# ORD_BYPASS.net
KiCad netlist of a schematic drawn in Altium Designer
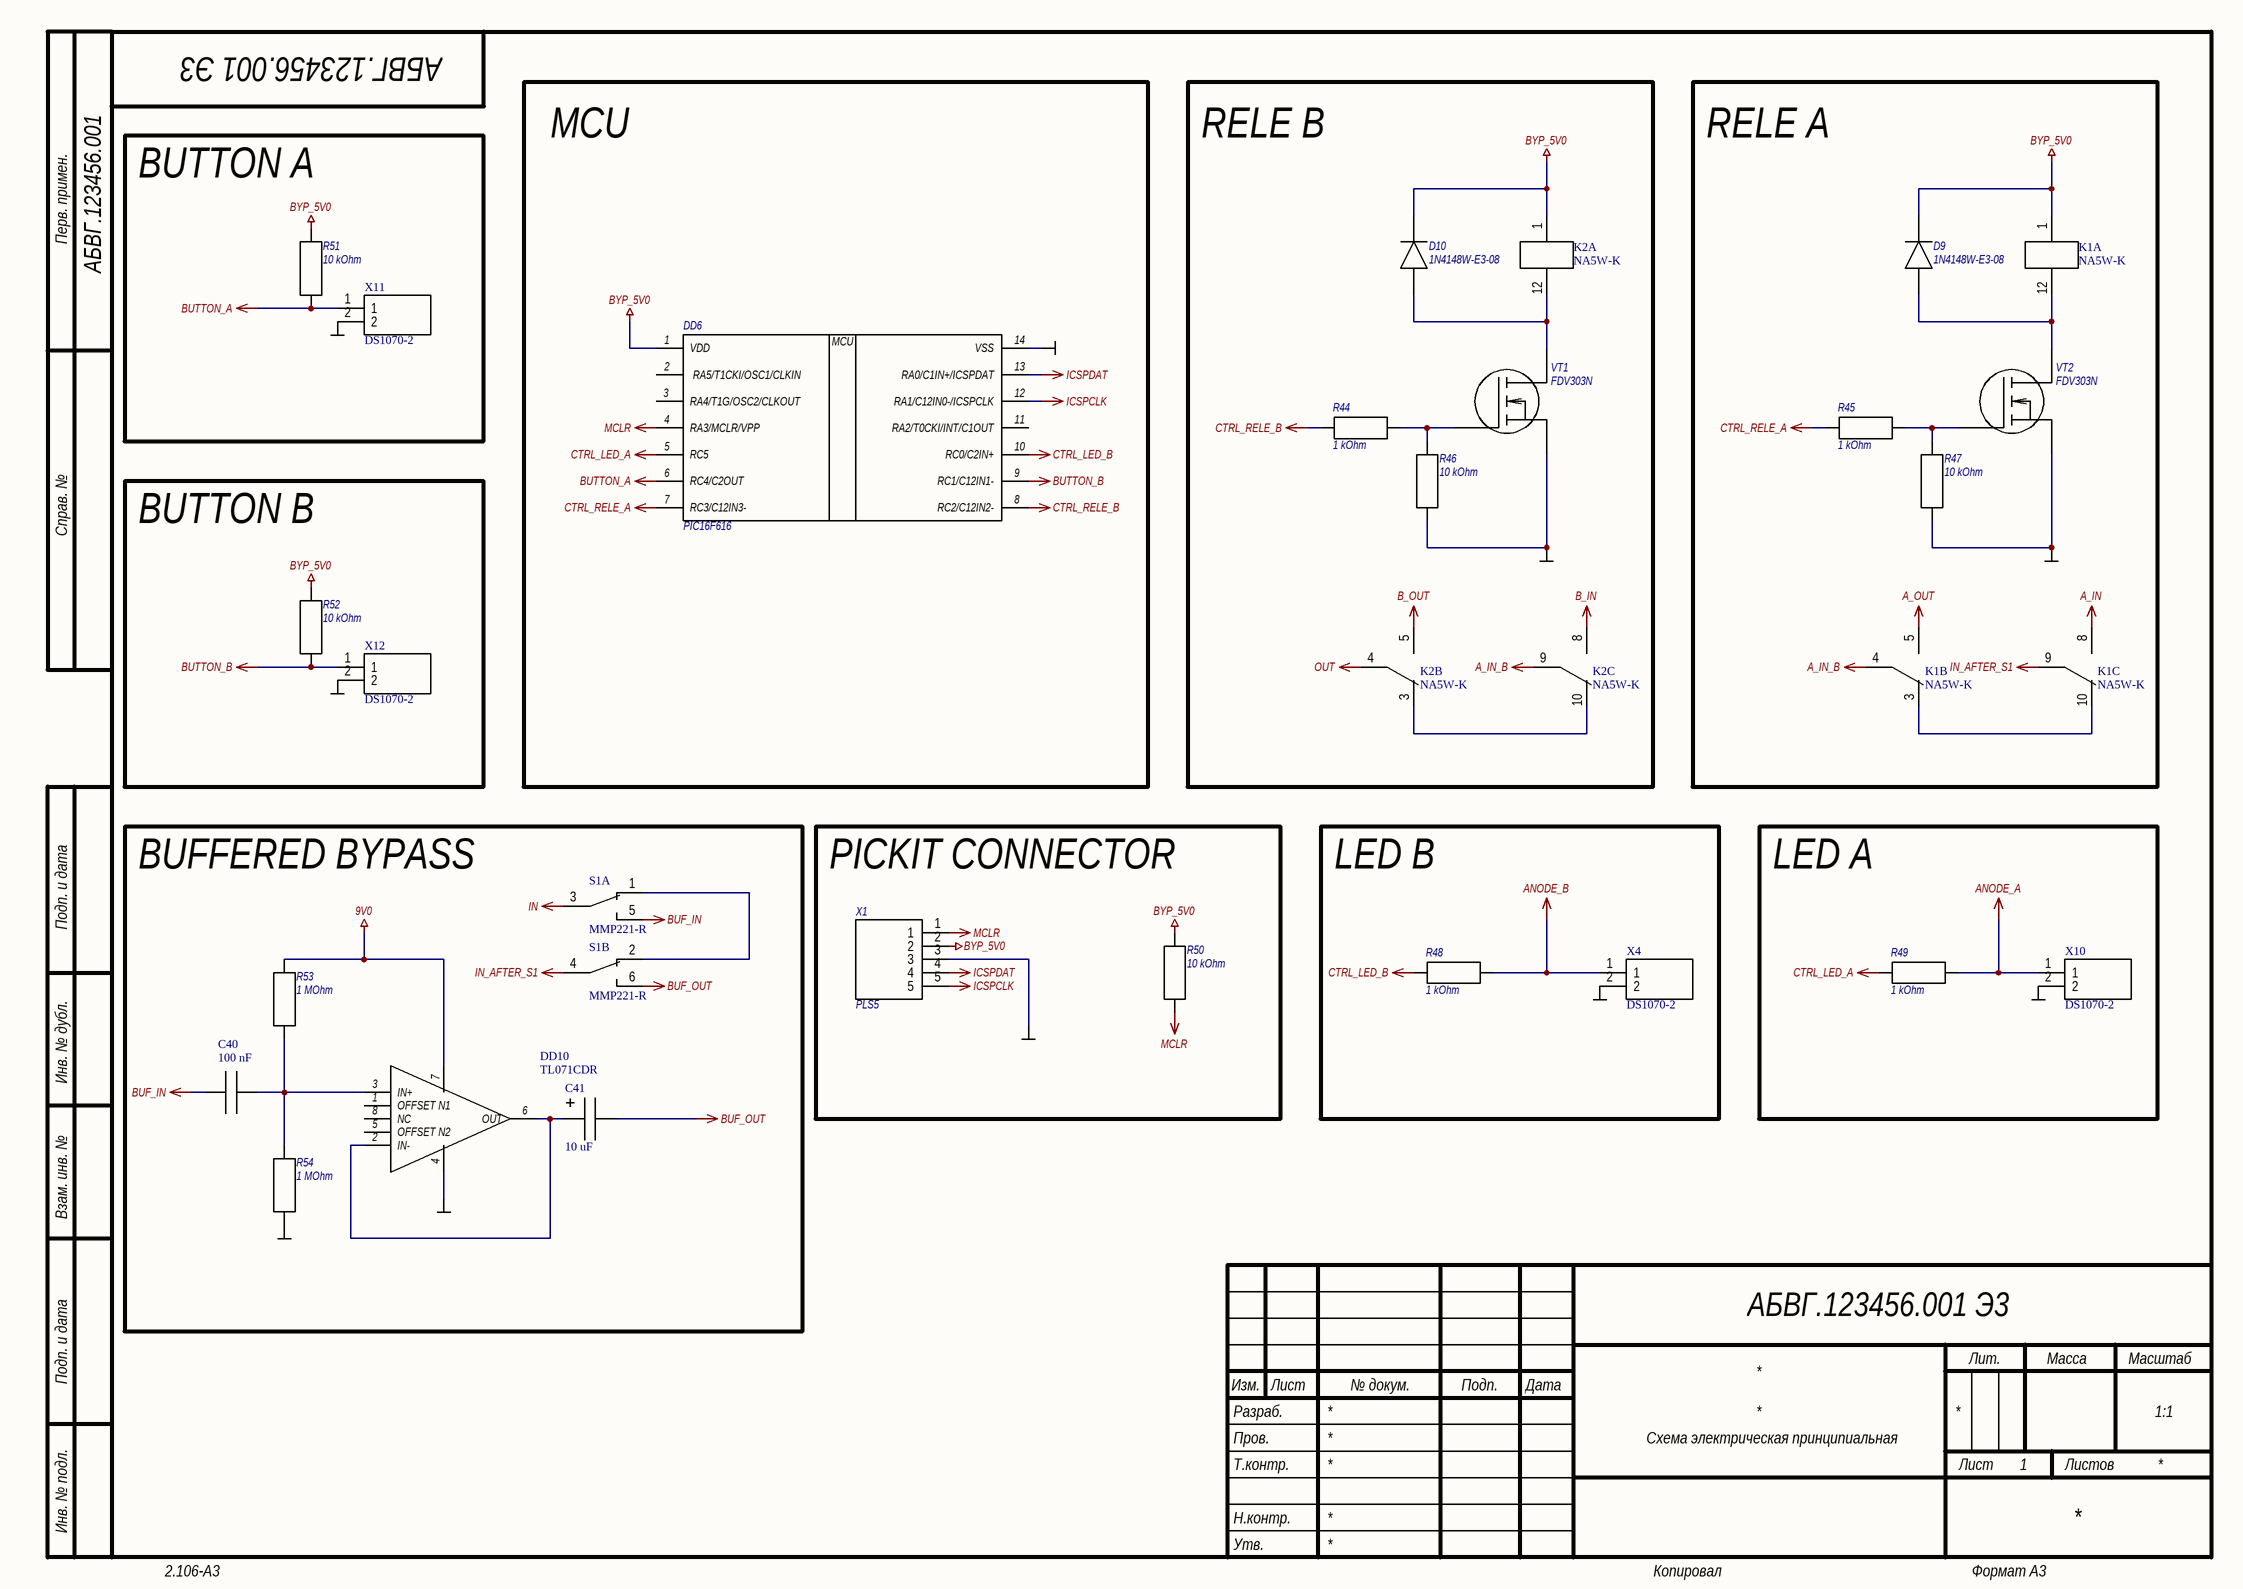
[diagram p0: ORD_BYPASS.SchDoc]

(export (version "E")
  (design (tool "Eeschema 10.0.6"))
  (components
    (comp (ref "C40")
      (value "100 nF")
      (footprint "C0805[2012]")
      (libsource (lib "Gost_passive_lib") (part "Capacitor"))
    )
    (comp (ref "C41")
      (value "10 uF")
      (footprint "C3216_CASE-A")
      (libsource (lib "Gost_passive_lib") (part "Capacitor_Pol"))
    )
    (comp (ref "D9")
      (value "1N4148W-E3-08")
      (footprint "SOD123")
      (description "Diode Switching 100V 0.15A SOD123 Vishay 1N4148W-E3-08 Switching Diode, 150mA 75V, 2-Pin SOD-123")
      (fields (field (name "RS PART NUMBER") "9189694"))
      (libsource (lib "Gost_passive_lib") (part "1N4148W-E3-08"))
    )
    (comp (ref "D10")
      (value "1N4148W-E3-08")
      (footprint "SOD123")
      (description "Diode Switching 100V 0.15A SOD123 Vishay 1N4148W-E3-08 Switching Diode, 150mA 75V, 2-Pin SOD-123")
      (fields (field (name "RS PART NUMBER") "9189694"))
      (libsource (lib "Gost_passive_lib") (part "1N4148W-E3-08"))
    )
    (comp (ref "DD6")
      (value "PIC16F616")
      (footprint "SO14")
      (description "Flash-Based 8-Bit\r\nCMOS Microcontroller")
      (fields
        (field (name "MANUFACTURER_PART_NUMBER") "LM386M-1/NOPB")
        (field (name "MOUSER PART NUMBER") "926-LM386M-1/NOPB")
      )
      (libsource (lib "Gost_active_libs") (part "PIC16F616"))
    )
    (comp (ref "DD10")
      (value "TL071CDR")
      (footprint "SO8")
      (description "TL071CDR, Operational Amplifier 4 MHz -18 to 18V, 8-Pin SO")
      (fields
        (field (name "MANUFACTURER_PART_NUMBER") "LM358DT")
        (field (name "MOUSER PART NUMBER") "511-LM358DT")
      )
      (libsource (lib "Gost_active_libs") (part "TL071CDR"))
    )
    (comp (ref "K1")
      (value "NA5W-K")
      (footprint "NA5W-K")
      (description "Low Signal Relays - PCB Mini Signal 5VDC")
      (fields
        (field (name "MANUFACTURER_PART_NUMBER") "NA-5W-K")
        (field (name "MOUSER PART NUMBER") "817-NA-5W-K")
      )
      (libsource (lib "Gost_passive_lib") (part "NA5W-K"))
    )
    (comp (ref "K2")
      (value "NA5W-K")
      (footprint "NA5W-K")
      (description "Low Signal Relays - PCB Mini Signal 5VDC")
      (fields
        (field (name "MANUFACTURER_PART_NUMBER") "NA-5W-K")
        (field (name "MOUSER PART NUMBER") "817-NA-5W-K")
      )
      (libsource (lib "Gost_passive_lib") (part "NA5W-K"))
    )
    (comp (ref "R44")
      (value "1 kOhm")
      (footprint "R0805[2012]")
      (libsource (lib "Gost_passive_lib") (part "Resistor"))
    )
    (comp (ref "R45")
      (value "1 kOhm")
      (footprint "R0805[2012]")
      (libsource (lib "Gost_passive_lib") (part "Resistor"))
    )
    (comp (ref "R46")
      (value "10 kOhm")
      (footprint "R0805[2012]")
      (libsource (lib "Gost_passive_lib") (part "Resistor"))
    )
    (comp (ref "R47")
      (value "10 kOhm")
      (footprint "R0805[2012]")
      (libsource (lib "Gost_passive_lib") (part "Resistor"))
    )
    (comp (ref "R48")
      (value "1 kOhm")
      (footprint "R0805[2012]")
      (libsource (lib "Gost_passive_lib") (part "Resistor"))
    )
    (comp (ref "R49")
      (value "1 kOhm")
      (footprint "R0805[2012]")
      (libsource (lib "Gost_passive_lib") (part "Resistor"))
    )
    (comp (ref "R50")
      (value "10 kOhm")
      (footprint "R0805[2012]")
      (libsource (lib "Gost_passive_lib") (part "Resistor"))
    )
    (comp (ref "R51")
      (value "10 kOhm")
      (footprint "R0805[2012]")
      (libsource (lib "Gost_passive_lib") (part "Resistor"))
    )
    (comp (ref "R52")
      (value "10 kOhm")
      (footprint "R0805[2012]")
      (libsource (lib "Gost_passive_lib") (part "Resistor"))
    )
    (comp (ref "R53")
      (value "1 MOhm")
      (footprint "R0805[2012]")
      (libsource (lib "Gost_passive_lib") (part "Resistor"))
    )
    (comp (ref "R54")
      (value "1 MOhm")
      (footprint "R0805[2012]")
      (libsource (lib "Gost_passive_lib") (part "Resistor"))
    )
    (comp (ref "S1")
      (value "MMP221-R")
      (footprint "MMP221R")
      (description "PCB Slide Switch DPDT On-On 200 mA @ 12 V dc Slide")
      (fields (field (name "RS PART NUMBER") "7023564P"))
      (libsource (lib "Gost_connectors_lib") (part "MMP221-R"))
    )
    (comp (ref "VT1")
      (value "FDV303N")
      (footprint "SOT-23")
      (description "N - channel power mosfet")
      (libsource (lib "Gost_passive_lib") (part "FDV303N"))
    )
    (comp (ref "VT2")
      (value "FDV303N")
      (footprint "SOT-23")
      (description "N - channel power mosfet")
      (libsource (lib "Gost_passive_lib") (part "FDV303N"))
    )
    (comp (ref "X1")
      (value "PLS5")
      (footprint "PLS-5 (UP)")
      (description "2.54 mm")
      (libsource (lib "Gost_connectors_lib") (part "PLS5"))
    )
    (comp (ref "X4")
      (value "DS1070-2")
      (footprint "DS1070-2")
      (description "2.54 mm, male")
      (libsource (lib "Gost_connectors_lib") (part "DS1070-2"))
    )
    (comp (ref "X10")
      (value "DS1070-2")
      (footprint "DS1070-2")
      (description "2.54 mm, male")
      (libsource (lib "Gost_connectors_lib") (part "DS1070-2"))
    )
    (comp (ref "X11")
      (value "DS1070-2")
      (footprint "DS1070-2")
      (description "2.54 mm, male")
      (libsource (lib "Gost_connectors_lib") (part "DS1070-2"))
    )
    (comp (ref "X12")
      (value "DS1070-2")
      (footprint "DS1070-2")
      (description "2.54 mm, male")
      (libsource (lib "Gost_connectors_lib") (part "DS1070-2"))
    )
  )
  (nets
    (net (code "1") (name "9V0") (class "Default")
      (node (ref "DD10") (pin "7") (pinfunction "VCC+_7") (pintype "passive"))
      (node (ref "R53") (pin "2") (pinfunction "2_2") (pintype "passive"))
    )
    (net (code "2") (name "ANODE_A") (class "Default")
      (node (ref "R49") (pin "2") (pinfunction "2_2") (pintype "passive"))
      (node (ref "X10") (pin "1") (pinfunction "1_1") (pintype "power_in"))
    )
    (net (code "3") (name "ANODE_B") (class "Default")
      (node (ref "R48") (pin "2") (pinfunction "2_2") (pintype "passive"))
      (node (ref "X4") (pin "1") (pinfunction "1_1") (pintype "power_in"))
    )
    (net (code "4") (name "A_IN") (class "Default")
      (node (ref "K1") (pin "8") (pinfunction "NO_2_8") (pintype "passive"))
    )
    (net (code "5") (name "A_IN_B") (class "Default")
      (node (ref "K1") (pin "4") (pinfunction "COM_1_4") (pintype "passive"))
      (node (ref "K2") (pin "9") (pinfunction "COM_2_9") (pintype "passive"))
    )
    (net (code "6") (name "A_OUT") (class "Default")
      (node (ref "K1") (pin "5") (pinfunction "NO_1_5") (pintype "passive"))
    )
    (net (code "7") (name "BUF_IN") (class "Default")
      (node (ref "C40") (pin "1") (pinfunction "1_1") (pintype "passive"))
      (node (ref "S1") (pin "5") (pinfunction "NO_1_5") (pintype "passive"))
    )
    (net (code "8") (name "BUF_OUT") (class "Default")
      (node (ref "C41") (pin "2") (pinfunction "2_2") (pintype "passive"))
      (node (ref "S1") (pin "6") (pinfunction "NO_2_6") (pintype "passive"))
    )
    (net (code "9") (name "BUTTON_A") (class "Default")
      (node (ref "DD6") (pin "6") (pinfunction "RC4/C2OUT_6") (pintype "passive"))
      (node (ref "R51") (pin "1") (pinfunction "1_1") (pintype "passive"))
      (node (ref "X11") (pin "1") (pinfunction "1_1") (pintype "power_in"))
    )
    (net (code "10") (name "BUTTON_B") (class "Default")
      (node (ref "DD6") (pin "9") (pinfunction "RC1/C12IN1-_9") (pintype "passive"))
      (node (ref "R52") (pin "1") (pinfunction "1_1") (pintype "passive"))
      (node (ref "X12") (pin "1") (pinfunction "1_1") (pintype "power_in"))
    )
    (net (code "11") (name "BYP_5V0") (class "Default")
      (node (ref "D10") (pin "1") (pinfunction "K_1") (pintype "passive"))
      (node (ref "D9") (pin "1") (pinfunction "K_1") (pintype "passive"))
      (node (ref "DD6") (pin "1") (pinfunction "VDD_1") (pintype "passive"))
      (node (ref "K1") (pin "1") (pinfunction "+(-)_1") (pintype "passive"))
      (node (ref "K2") (pin "1") (pinfunction "+(-)_1") (pintype "passive"))
      (node (ref "R50") (pin "2") (pinfunction "2_2") (pintype "passive"))
      (node (ref "R51") (pin "2") (pinfunction "2_2") (pintype "passive"))
      (node (ref "R52") (pin "2") (pinfunction "2_2") (pintype "passive"))
      (node (ref "X1") (pin "2") (pinfunction "2_2") (pintype "power_in"))
    )
    (net (code "12") (name "B_IN") (class "Default")
      (node (ref "K2") (pin "8") (pinfunction "NO_2_8") (pintype "passive"))
    )
    (net (code "13") (name "B_OUT") (class "Default")
      (node (ref "K2") (pin "5") (pinfunction "NO_1_5") (pintype "passive"))
    )
    (net (code "14") (name "CTRL_LED_A") (class "Default")
      (node (ref "DD6") (pin "5") (pinfunction "RC5_5") (pintype "passive"))
      (node (ref "R49") (pin "1") (pinfunction "1_1") (pintype "passive"))
    )
    (net (code "15") (name "CTRL_LED_B") (class "Default")
      (node (ref "DD6") (pin "10") (pinfunction "RC0/C2IN+_10") (pintype "passive"))
      (node (ref "R48") (pin "1") (pinfunction "1_1") (pintype "passive"))
    )
    (net (code "16") (name "CTRL_RELE_A") (class "Default")
      (node (ref "DD6") (pin "7") (pinfunction "RC3/C12IN3-_7") (pintype "passive"))
      (node (ref "R45") (pin "1") (pinfunction "1_1") (pintype "passive"))
    )
    (net (code "17") (name "CTRL_RELE_B") (class "Default")
      (node (ref "DD6") (pin "8") (pinfunction "RC2/C12IN2-_8") (pintype "passive"))
      (node (ref "R44") (pin "1") (pinfunction "1_1") (pintype "passive"))
    )
    (net (code "18") (name "GND") (class "Default")
      (node (ref "DD10") (pin "4") (pinfunction "VCC-_4") (pintype "passive"))
      (node (ref "DD6") (pin "14") (pinfunction "VSS_14") (pintype "passive"))
      (node (ref "R46") (pin "1") (pinfunction "1_1") (pintype "passive"))
      (node (ref "R47") (pin "1") (pinfunction "1_1") (pintype "passive"))
      (node (ref "R54") (pin "1") (pinfunction "1_1") (pintype "passive"))
      (node (ref "VT1") (pin "2") (pinfunction "S_2") (pintype "passive"))
      (node (ref "VT2") (pin "2") (pinfunction "S_2") (pintype "passive"))
      (node (ref "X1") (pin "3") (pinfunction "3_3") (pintype "power_in"))
      (node (ref "X10") (pin "2") (pinfunction "2_2") (pintype "power_in"))
      (node (ref "X11") (pin "2") (pinfunction "2_2") (pintype "power_in"))
      (node (ref "X12") (pin "2") (pinfunction "2_2") (pintype "power_in"))
      (node (ref "X4") (pin "2") (pinfunction "2_2") (pintype "power_in"))
    )
    (net (code "19") (name "ICSPCLK") (class "Default")
      (node (ref "DD6") (pin "12") (pinfunction "RA1/C12IN0-/ICSPCLK_12") (pintype "passive"))
      (node (ref "X1") (pin "5") (pinfunction "5_5") (pintype "power_in"))
    )
    (net (code "20") (name "ICSPDAT") (class "Default")
      (node (ref "DD6") (pin "13") (pinfunction "RA0/C1IN+/ICSPDAT_13") (pintype "passive"))
      (node (ref "X1") (pin "4") (pinfunction "4_4") (pintype "power_in"))
    )
    (net (code "21") (name "IN") (class "Default")
      (node (ref "S1") (pin "3") (pinfunction "C_1_3") (pintype "passive"))
    )
    (net (code "22") (name "IN_AFTER_S1") (class "Default")
      (node (ref "K1") (pin "9") (pinfunction "COM_2_9") (pintype "passive"))
      (node (ref "S1") (pin "4") (pinfunction "C_2_4") (pintype "passive"))
    )
    (net (code "23") (name "MCLR") (class "Default")
      (node (ref "DD6") (pin "4") (pinfunction "RA3/MCLR/VPP_4") (pintype "passive"))
      (node (ref "R50") (pin "1") (pinfunction "1_1") (pintype "passive"))
      (node (ref "X1") (pin "1") (pinfunction "1_1") (pintype "power_in"))
    )
    (net (code "24") (name "Net-(D9-A)") (class "Default")
      (node (ref "D9") (pin "2") (pinfunction "A_2") (pintype "passive"))
      (node (ref "K1") (pin "12") (pinfunction "-(+)_12") (pintype "passive"))
      (node (ref "VT2") (pin "3") (pinfunction "D_3") (pintype "passive"))
    )
    (net (code "25") (name "Net-(D10-A)") (class "Default")
      (node (ref "D10") (pin "2") (pinfunction "A_2") (pintype "passive"))
      (node (ref "K2") (pin "12") (pinfunction "-(+)_12") (pintype "passive"))
      (node (ref "VT1") (pin "3") (pinfunction "D_3") (pintype "passive"))
    )
    (net (code "26") (name "Net-(DD10-IN+)") (class "Default")
      (node (ref "C40") (pin "2") (pinfunction "2_2") (pintype "passive"))
      (node (ref "DD10") (pin "3") (pinfunction "IN+_3") (pintype "passive"))
      (node (ref "R53") (pin "1") (pinfunction "1_1") (pintype "passive"))
      (node (ref "R54") (pin "2") (pinfunction "2_2") (pintype "passive"))
    )
    (net (code "27") (name "Net-(DD10-IN-)") (class "Default")
      (node (ref "C41") (pin "1") (pinfunction "1_1") (pintype "passive"))
      (node (ref "DD10") (pin "2") (pinfunction "IN-_2") (pintype "passive"))
      (node (ref "DD10") (pin "6") (pinfunction "OUT_6") (pintype "passive"))
    )
    (net (code "28") (name "Net-(K1B-NC_1)") (class "Default")
      (node (ref "K1") (pin "10") (pinfunction "NC_2_10") (pintype "passive"))
      (node (ref "K1") (pin "3") (pinfunction "NC_1_3") (pintype "passive"))
    )
    (net (code "29") (name "Net-(K2B-NC_1)") (class "Default")
      (node (ref "K2") (pin "10") (pinfunction "NC_2_10") (pintype "passive"))
      (node (ref "K2") (pin "3") (pinfunction "NC_1_3") (pintype "passive"))
    )
    (net (code "30") (name "Net-(S1A-NC_1)") (class "Default")
      (node (ref "S1") (pin "1") (pinfunction "NC_1_1") (pintype "passive"))
      (node (ref "S1") (pin "2") (pinfunction "NC_2_2") (pintype "passive"))
    )
    (net (code "31") (name "Net-(VT1-G)") (class "Default")
      (node (ref "R44") (pin "2") (pinfunction "2_2") (pintype "passive"))
      (node (ref "R46") (pin "2") (pinfunction "2_2") (pintype "passive"))
      (node (ref "VT1") (pin "1") (pinfunction "G_1") (pintype "passive"))
    )
    (net (code "32") (name "Net-(VT2-G)") (class "Default")
      (node (ref "R45") (pin "2") (pinfunction "2_2") (pintype "passive"))
      (node (ref "R47") (pin "2") (pinfunction "2_2") (pintype "passive"))
      (node (ref "VT2") (pin "1") (pinfunction "G_1") (pintype "passive"))
    )
    (net (code "33") (name "OUT") (class "Default")
      (node (ref "K2") (pin "4") (pinfunction "COM_1_4") (pintype "passive"))
    )
    (net (code "34") (name "unconnected-(DD6-RA2{slash}T0CKI{slash}INT{slash}C1OUT-Pad11)") (class "Default")
      (node (ref "DD6") (pin "11") (pinfunction "RA2/T0CKI/INT/C1OUT_11") (pintype "passive"))
    )
    (net (code "35") (name "unconnected-(DD6-RA4{slash}T1G{slash}OSC2{slash}CLKOUT-Pad3)") (class "Default")
      (node (ref "DD6") (pin "3") (pinfunction "RA4/T1G/OSC2/CLKOUT_3") (pintype "passive"))
    )
    (net (code "36") (name "unconnected-(DD6-RA5{slash}T1CKI{slash}OSC1{slash}CLKIN-Pad2)") (class "Default")
      (node (ref "DD6") (pin "2") (pinfunction "RA5/T1CKI/OSC1/CLKIN_2") (pintype "passive"))
    )
    (net (code "37") (name "unconnected-(DD10-NC-Pad8)") (class "Default")
      (node (ref "DD10") (pin "8") (pinfunction "NC_8") (pintype "passive"))
    )
    (net (code "38") (name "unconnected-(DD10-OFFSET_N1-Pad1)") (class "Default")
      (node (ref "DD10") (pin "1") (pinfunction "OFFSET_N1_1") (pintype "power_in"))
    )
    (net (code "39") (name "unconnected-(DD10-OFFSET_N2-Pad5)") (class "Default")
      (node (ref "DD10") (pin "5") (pinfunction "OFFSET_N2_5") (pintype "power_in"))
    )
  )
)
